# PenguinPi.net
KiCad netlist of a schematic drawn in Altium Designer
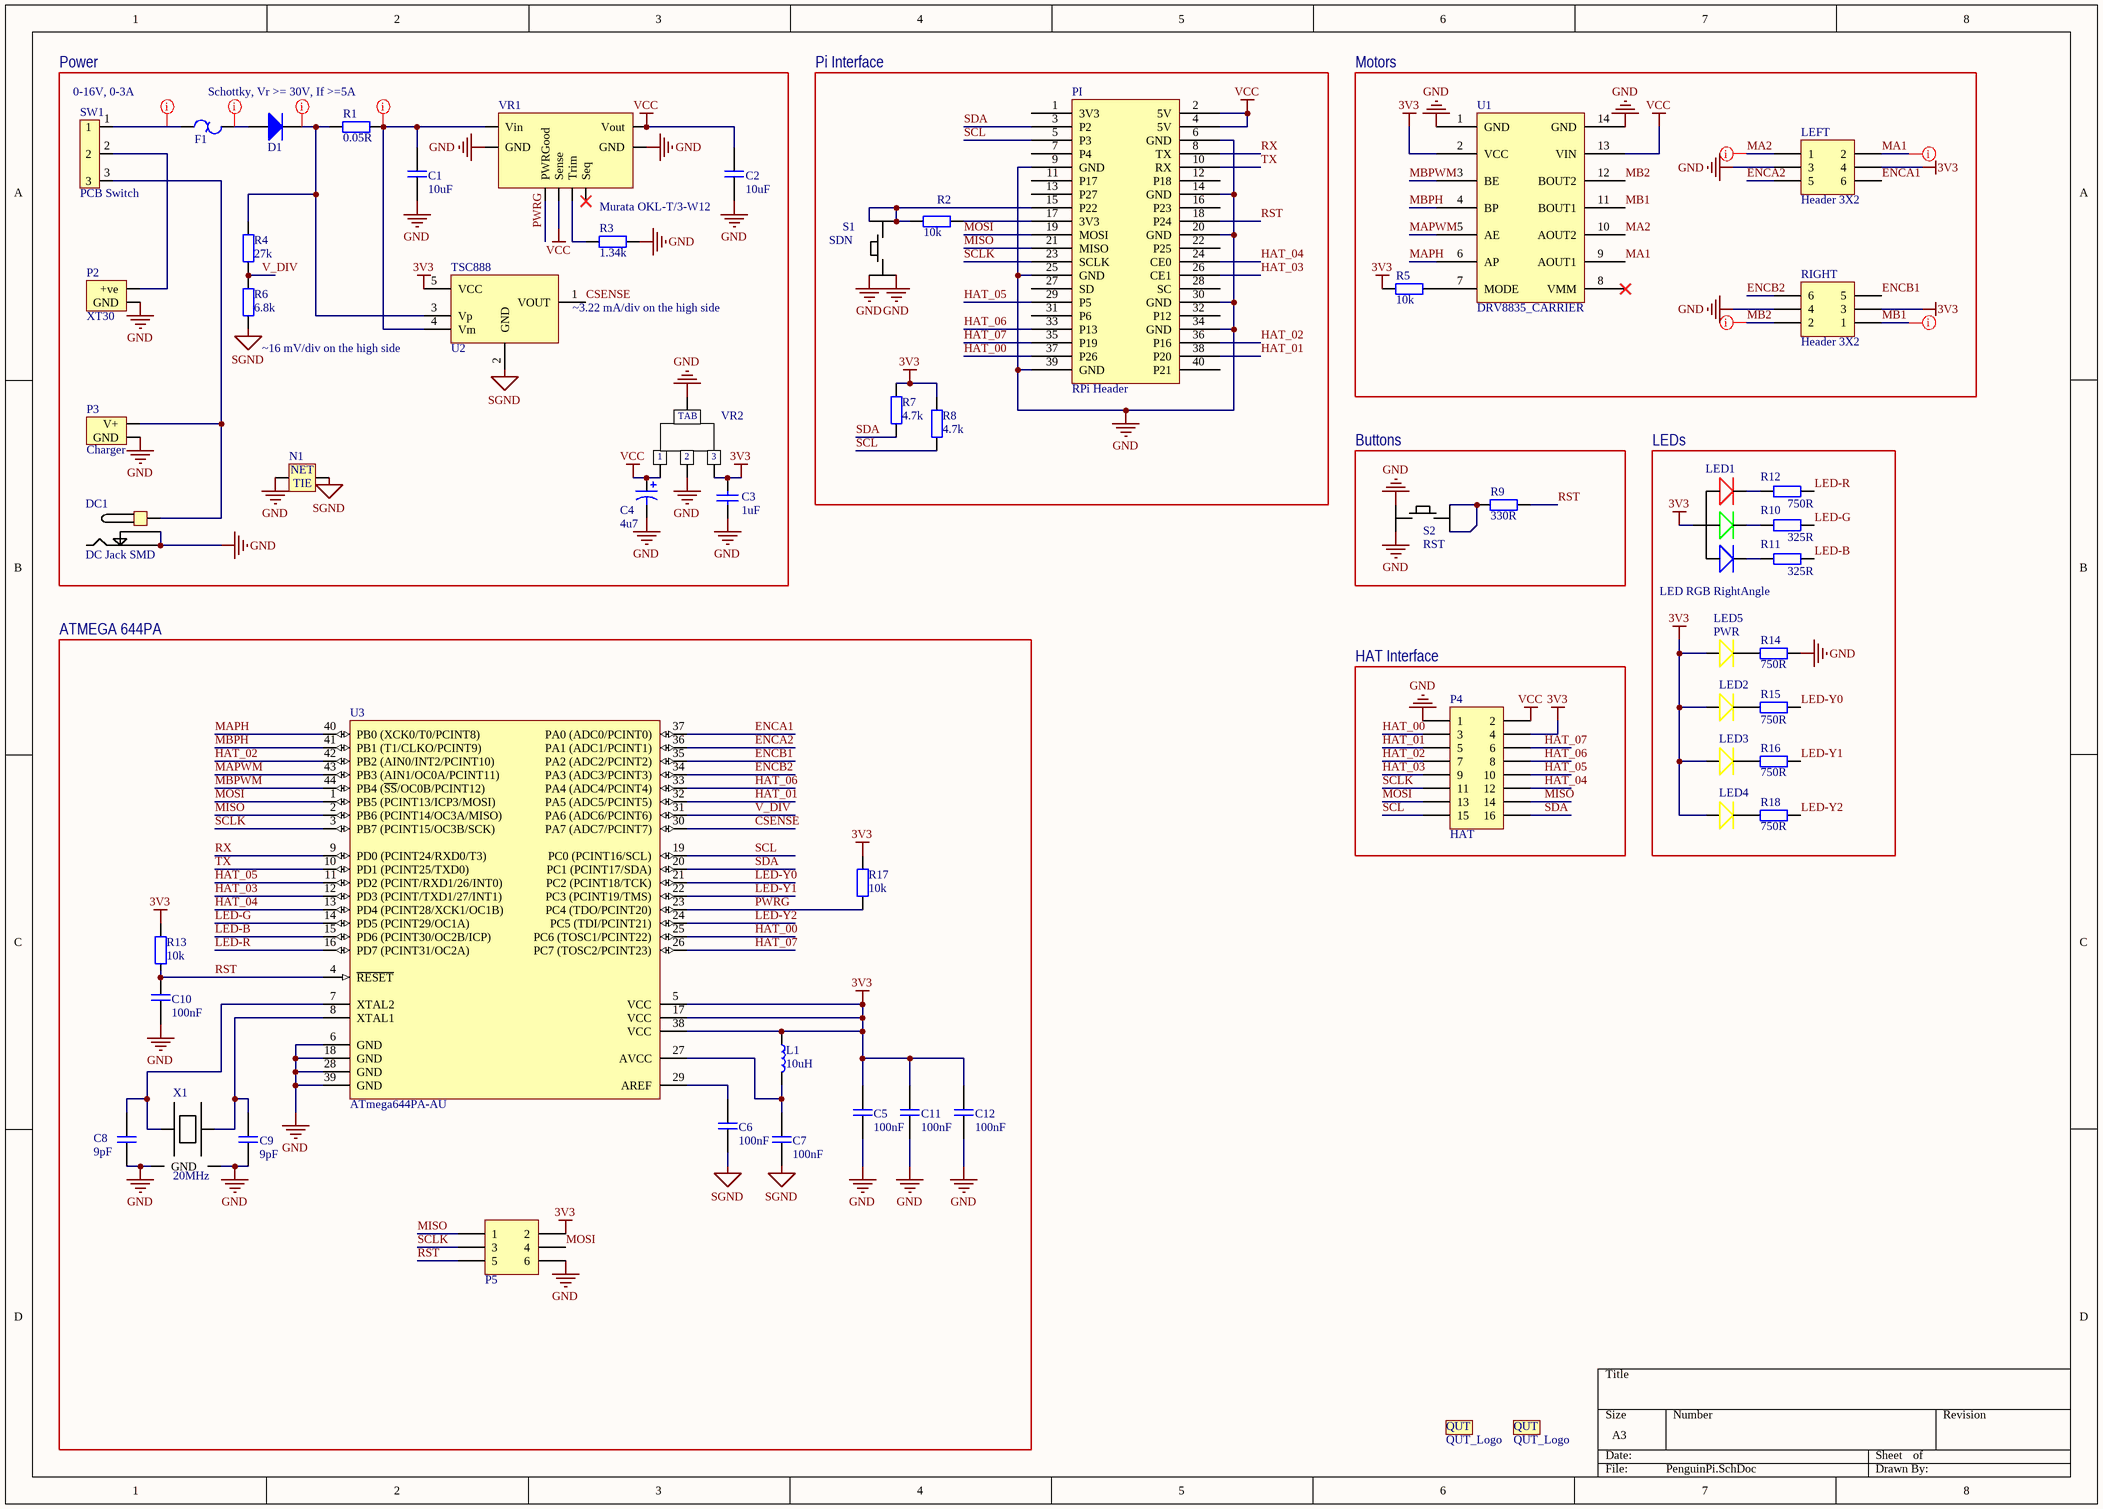
[diagram p0: PenguinPi.SchDoc]

(export (version "E")
  (design (tool "Eeschema 10.0.6"))
  (components
    (comp (ref "C1")
      (value "10uF")
      (footprint "CAPC2012X07N")
      (description "Surface mount capacitor")
      (fields (field (name "Comment") "CAP SMD"))
      (libsource (lib "Penguin") (part "CAP SMD"))
    )
    (comp (ref "C2")
      (value "10uF")
      (footprint "CAPC2012X07N")
      (description "Surface mount capacitor")
      (fields (field (name "Comment") "CAP SMD"))
      (libsource (lib "Penguin") (part "CAP SMD"))
    )
    (comp (ref "C3")
      (value "1uF")
      (footprint "6-0805_M")
      (description "Capacitor")
      (fields (field (name "Comment") "Cap") (field (name "PUBLISHER") "Altium Limited"))
      (libsource (lib "Miscellaneous Devices") (part "Cap"))
    )
    (comp (ref "C4")
      (value "4u7")
      (footprint "6-0805_M")
      (description "Polarized Capacitor (Radial)")
      (fields (field (name "Comment") "Cap Pol1") (field (name "PUBLISHER") "Altium Limited"))
      (libsource (lib "Miscellaneous Devices") (part "Cap Pol1"))
    )
    (comp (ref "C5")
      (value "100nF")
      (footprint "CAPC2012X07N")
      (description "Surface mount capacitor")
      (fields (field (name "Comment") "CAP SMD"))
      (libsource (lib "Penguin") (part "CAP SMD"))
    )
    (comp (ref "C6")
      (value "100nF")
      (footprint "CAPC2012X07N")
      (description "Surface mount capacitor")
      (fields (field (name "Comment") "CAP SMD"))
      (libsource (lib "Penguin") (part "CAP SMD"))
    )
    (comp (ref "C7")
      (value "100nF")
      (footprint "CAPC2012X07N")
      (description "Surface mount capacitor")
      (fields (field (name "Comment") "CAP SMD"))
      (libsource (lib "Penguin") (part "CAP SMD"))
    )
    (comp (ref "C8")
      (value "9pF")
      (footprint "CAPC2012X07N")
      (description "Surface mount capacitor")
      (fields (field (name "Comment") "CAP SMD"))
      (libsource (lib "Penguin") (part "CAP SMD"))
    )
    (comp (ref "C9")
      (value "9pF")
      (footprint "CAPC2012X07N")
      (description "Surface mount capacitor")
      (fields (field (name "Comment") "CAP SMD"))
      (libsource (lib "Penguin") (part "CAP SMD"))
    )
    (comp (ref "C10")
      (value "100nF")
      (footprint "CAPC2012X07N")
      (description "Surface mount capacitor")
      (fields (field (name "Comment") "CAP SMD"))
      (libsource (lib "Penguin") (part "CAP SMD"))
    )
    (comp (ref "C11")
      (value "100nF")
      (footprint "CAPC2012X07N")
      (description "Surface mount capacitor")
      (fields (field (name "Comment") "CAP SMD"))
      (libsource (lib "Penguin") (part "CAP SMD"))
    )
    (comp (ref "C12")
      (value "100nF")
      (footprint "CAPC2012X07N")
      (description "Surface mount capacitor")
      (fields (field (name "Comment") "CAP SMD"))
      (libsource (lib "Penguin") (part "CAP SMD"))
    )
    (comp (ref "D1")
      (value "SMD DIODE")
      (footprint "SODFL470X110-2N")
      (description "Surface mount Diode")
      (libsource (lib "Penguin") (part "SMD DIODE"))
    )
    (comp (ref "DC1")
      (value "DC Jack SMD")
      (footprint "DC Jack SMD")
      (libsource (lib "QUT") (part "DC Jack SMD"))
    )
    (comp (ref "F1")
      (value "RGEF250")
      (footprint "MF-MSMF250/16X-2")
      (description "PPTC Thermal Fuse")
      (libsource (lib "Penguin") (part "RGEF250"))
    )
    (comp (ref "L1")
      (value "10uH")
      (footprint "CM322522")
      (description "Surface Mount Inductor - varying sizes")
      (fields (field (name "Comment") "INDUCTOR SMD"))
      (libsource (lib "Penguin") (part "INDUCTOR SMD"))
    )
    (comp (ref "LED1")
      (value "LED RGB RightAngle")
      (footprint "LED RGB RightAngle")
      (libsource (lib "PenguinPi_v2") (part "LED RGB RightAngle"))
    )
    (comp (ref "LED2")
      (value "~")
      (footprint "LED YELLOW RightAngle")
      (libsource (lib "PenguinPi_v2") (part "LED Yellow RightAngle"))
    )
    (comp (ref "LED3")
      (value "~")
      (footprint "LED YELLOW RightAngle")
      (libsource (lib "PenguinPi_v2") (part "LED Yellow RightAngle"))
    )
    (comp (ref "LED4")
      (value "~")
      (footprint "LED YELLOW RightAngle")
      (libsource (lib "PenguinPi_v2") (part "LED Yellow RightAngle"))
    )
    (comp (ref "LED5")
      (value "PWR")
      (footprint "LED YELLOW RightAngle")
      (libsource (lib "PenguinPi_v2") (part "LED Yellow RightAngle"))
    )
    (comp (ref "LEFT")
      (value "Header 3X2")
      (footprint "HDR2X3")
      (description "Header, 3-Pin, Dual row")
      (fields (field (name "PUBLISHER") "Altium Limited"))
      (libsource (lib "") (part "Header 3X2_1"))
    )
    (comp (ref "LG1") (value "QUT_Logo") (footprint "QUT_Logo") (libsource (lib "Penguin") (part "QUT_Logo")))
    (comp (ref "LG2") (value "QUT_Logo") (footprint "QUT_Logo") (libsource (lib "Penguin") (part "QUT_Logo")))
    (comp (ref "N1")
      (value "NETTIE")
      (footprint "NETTIE-SMD-5mil")
      (libsource (lib "Penguin") (part "NETTIE"))
    )
    (comp (ref "P2") (value "XT30") (footprint "XT30 - PCB mount") (libsource (lib "QUT") (part "XT30")))
    (comp (ref "P3")
      (value "Charger")
      (footprint "Molex SL70553 2 way")
      (fields (field (name "MANUFACTURER") "Molex") (field (name "MANUFACTURER PART NO") "70553-0001"))
      (libsource (lib "QUT") (part "Molex SL 70553 2way"))
    )
    (comp (ref "P4")
      (value "HAT")
      (footprint "HDR2X8")
      (description "Header, 8-Pin, Dual row")
      (fields (field (name "PUBLISHER") "Altium Limited"))
      (libsource (lib "Miscellaneous Connectors") (part "Header 8X2"))
    )
    (comp (ref "P5")
      (value "ISP")
      (footprint "Header 3x2 nonstandard")
      (description "3 by 2 header, staggered pin arrangement")
      (libsource (lib "Penguin") (part "Header 3x2 Staggered"))
    )
    (comp (ref "PI")
      (value "RPi Header")
      (footprint "RPI 2 Header")
      (description "GPIO connector for Raspberry Pi Microcomputer")
      (libsource (lib "Penguin") (part "RPi 2 Header"))
    )
    (comp (ref "R1")
      (value "0.05R")
      (footprint "RESC3216X06M")
      (description "0805 surface mount resistor")
      (fields (field (name "Comment") "RES SMD"))
      (libsource (lib "") (part "RES SMD_2"))
    )
    (comp (ref "R2")
      (value "10k")
      (footprint "RESC2012X07N")
      (description "0805 surface mount resistor")
      (fields (field (name "Comment") "RES SMD"))
      (libsource (lib "Penguin") (part "RES SMD"))
    )
    (comp (ref "R3")
      (value "1.34k")
      (footprint "RESC2012X07N")
      (description "0805 surface mount resistor")
      (fields (field (name "Comment") "RES SMD"))
      (libsource (lib "") (part "RES SMD_3"))
    )
    (comp (ref "R4")
      (value "27k")
      (footprint "RESC2012X07N")
      (description "0805 surface mount resistor")
      (fields (field (name "Comment") "RES SMD"))
      (libsource (lib "") (part "RES SMD_1"))
    )
    (comp (ref "R5")
      (value "10k")
      (footprint "RESC2012X07N")
      (description "0805 surface mount resistor")
      (fields (field (name "Comment") "RES SMD"))
      (libsource (lib "Penguin") (part "RES SMD"))
    )
    (comp (ref "R6")
      (value "6.8k")
      (footprint "RESC2012X07N")
      (description "0805 surface mount resistor")
      (fields (field (name "Comment") "RES SMD"))
      (libsource (lib "") (part "RES SMD_1"))
    )
    (comp (ref "R7")
      (value "4.7k")
      (footprint "RESC2012X07N")
      (description "0805 surface mount resistor")
      (fields (field (name "Comment") "RES SMD"))
      (libsource (lib "") (part "RES SMD_1"))
    )
    (comp (ref "R8")
      (value "4.7k")
      (footprint "RESC2012X07N")
      (description "0805 surface mount resistor")
      (fields (field (name "Comment") "RES SMD"))
      (libsource (lib "") (part "RES SMD_1"))
    )
    (comp (ref "R9")
      (value "330R")
      (footprint "RESC2012X07N")
      (description "0805 surface mount resistor")
      (fields (field (name "Comment") "RES SMD"))
      (libsource (lib "Penguin") (part "RES SMD"))
    )
    (comp (ref "R10")
      (value "325R")
      (footprint "RESC2012X07N")
      (description "0805 surface mount resistor")
      (fields (field (name "Comment") "RES SMD"))
      (libsource (lib "Penguin") (part "RES SMD"))
    )
    (comp (ref "R11")
      (value "325R")
      (footprint "RESC2012X07N")
      (description "0805 surface mount resistor")
      (fields (field (name "Comment") "RES SMD"))
      (libsource (lib "Penguin") (part "RES SMD"))
    )
    (comp (ref "R12")
      (value "750R")
      (footprint "RESC2012X07N")
      (description "0805 surface mount resistor")
      (fields (field (name "Comment") "RES SMD"))
      (libsource (lib "Penguin") (part "RES SMD"))
    )
    (comp (ref "R13")
      (value "10k")
      (footprint "RESC2012X07N")
      (description "0805 surface mount resistor")
      (fields (field (name "Comment") "RES SMD"))
      (libsource (lib "") (part "RES SMD_1"))
    )
    (comp (ref "R14")
      (value "750R")
      (footprint "RESC2012X07N")
      (description "0805 surface mount resistor")
      (fields (field (name "Comment") "RES SMD"))
      (libsource (lib "Penguin") (part "RES SMD"))
    )
    (comp (ref "R15")
      (value "750R")
      (footprint "RESC2012X07N")
      (description "0805 surface mount resistor")
      (fields (field (name "Comment") "RES SMD"))
      (libsource (lib "Penguin") (part "RES SMD"))
    )
    (comp (ref "R16")
      (value "750R")
      (footprint "RESC2012X07N")
      (description "0805 surface mount resistor")
      (fields (field (name "Comment") "RES SMD"))
      (libsource (lib "Penguin") (part "RES SMD"))
    )
    (comp (ref "R17")
      (value "10k")
      (footprint "RESC2012X07N")
      (description "0805 surface mount resistor")
      (fields (field (name "Comment") "RES SMD"))
      (libsource (lib "") (part "RES SMD_1"))
    )
    (comp (ref "R18")
      (value "750R")
      (footprint "RESC2012X07N")
      (description "0805 surface mount resistor")
      (fields (field (name "Comment") "RES SMD"))
      (libsource (lib "Penguin") (part "RES SMD"))
    )
    (comp (ref "RIGHT")
      (value "Header 3X2")
      (footprint "HDR2X3")
      (description "Header, 3-Pin, Dual row")
      (fields (field (name "PUBLISHER") "Altium Limited"))
      (libsource (lib "Miscellaneous Connectors") (part "Header 3X2"))
    )
    (comp (ref "S1")
      (value "SDN")
      (footprint "E-SWITCH-TL3342")
      (description "TL 3342 surface mount pushbutton")
      (libsource (lib "Penguin") (part "E-SWITCH-PUSHBUTTON"))
    )
    (comp (ref "S2")
      (value "RST")
      (footprint "E-SWITCH-TL3342")
      (description "TL 3342 surface mount pushbutton")
      (libsource (lib "Penguin") (part "E-SWITCH-PUSHBUTTON"))
    )
    (comp (ref "SW1")
      (value "PCB Switch")
      (footprint "PCB Switch")
      (libsource (lib "PenguinPi_v2") (part "PCB Switch"))
    )
    (comp (ref "U1")
      (value "DRV8835_CARRIER")
      (footprint "DRV8835_CARRIER")
      (description "DRV8835 Motor Controller")
      (libsource (lib "Penguin") (part "DRV8835_CARRIER"))
    )
    (comp (ref "U2")
      (value "TSC888")
      (footprint "SOT95P280X145-5N")
      (description "Curent Sense Amplifier")
      (libsource (lib "Penguin") (part "TSC888"))
    )
    (comp (ref "U3")
      (value "ATmega644PA-AU")
      (footprint "44A_L")
      (libsource (lib "Altium Content Vault") (part "MC-8B-ATM128-SQ44"))
    )
    (comp (ref "VR1")
      (value "Murata OKL-T/3-W12")
      (footprint "OKL-T/3-W12")
      (libsource (lib "PenguinPi_v2") (part "Murata OKL-T/3-W12"))
    )
    (comp (ref "VR2") (value "FT_SOT223") (footprint "SOT233-4N") (libsource (lib "QUT") (part "FT_SOT223")))
    (comp (ref "X1") (value "20MHz") (footprint "XTAL TSX3225") (libsource (lib "QUT") (part "XTAL ABM3B")))
  )
  (nets
    (net (code "1") (name "/CSENSE") (class "Default")
      (node (ref "U2") (pin "1") (pinfunction "VOUT_1") (pintype "passive"))
      (node (ref "U3") (pin "30") (pinfunction "PA7_(ADC7/PCINT7)_30") (pintype "bidirectional"))
    )
    (net (code "2") (name "/ENCA1") (class "Default")
      (node (ref "LEFT") (pin "6") (pinfunction "6_6") (pintype "passive"))
      (node (ref "U3") (pin "37") (pinfunction "PA0_(ADC0/PCINT0)_37") (pintype "bidirectional"))
    )
    (net (code "3") (name "/ENCA2") (class "Default")
      (node (ref "LEFT") (pin "5") (pinfunction "5_5") (pintype "passive"))
      (node (ref "U3") (pin "36") (pinfunction "PA1_(ADC1/PCINT1)_36") (pintype "bidirectional"))
    )
    (net (code "4") (name "/ENCB1") (class "Default")
      (node (ref "RIGHT") (pin "5") (pinfunction "5_5") (pintype "passive"))
      (node (ref "U3") (pin "35") (pinfunction "PA2_(ADC2/PCINT2)_35") (pintype "bidirectional"))
    )
    (net (code "5") (name "/ENCB2") (class "Default")
      (node (ref "RIGHT") (pin "6") (pinfunction "6_6") (pintype "passive"))
      (node (ref "U3") (pin "34") (pinfunction "PA3_(ADC3/PCINT3)_34") (pintype "bidirectional"))
    )
    (net (code "6") (name "/HAT_00") (class "Default")
      (node (ref "P4") (pin "3") (pinfunction "3_3") (pintype "passive"))
      (node (ref "PI") (pin "37") (pinfunction "P26_37") (pintype "passive"))
      (node (ref "U3") (pin "25") (pinfunction "PC6_(TOSC1/PCINT22)_25") (pintype "bidirectional"))
    )
    (net (code "7") (name "/HAT_01") (class "Default")
      (node (ref "P4") (pin "5") (pinfunction "5_5") (pintype "passive"))
      (node (ref "PI") (pin "38") (pinfunction "P20_38") (pintype "passive"))
      (node (ref "U3") (pin "32") (pinfunction "PA5_(ADC5/PCINT5)_32") (pintype "bidirectional"))
    )
    (net (code "8") (name "/HAT_02") (class "Default")
      (node (ref "P4") (pin "7") (pinfunction "7_7") (pintype "passive"))
      (node (ref "PI") (pin "36") (pinfunction "P16_36") (pintype "passive"))
      (node (ref "U3") (pin "42") (pinfunction "PB2_(AIN0/INT2/PCINT10)_42") (pintype "bidirectional"))
    )
    (net (code "9") (name "/HAT_03") (class "Default")
      (node (ref "P4") (pin "9") (pinfunction "9_9") (pintype "passive"))
      (node (ref "PI") (pin "26") (pinfunction "CE1_26") (pintype "passive"))
      (node (ref "U3") (pin "12") (pinfunction "PD3_(PCINT/TXD1/27/INT1)_12") (pintype "bidirectional"))
    )
    (net (code "10") (name "/HAT_04") (class "Default")
      (node (ref "P4") (pin "12") (pinfunction "12_12") (pintype "passive"))
      (node (ref "PI") (pin "24") (pinfunction "CE0_24") (pintype "passive"))
      (node (ref "U3") (pin "13") (pinfunction "PD4_(PCINT28/XCK1/OC1B)_13") (pintype "bidirectional"))
    )
    (net (code "11") (name "/HAT_05") (class "Default")
      (node (ref "P4") (pin "10") (pinfunction "10_10") (pintype "passive"))
      (node (ref "PI") (pin "29") (pinfunction "P5_29") (pintype "passive"))
      (node (ref "U3") (pin "11") (pinfunction "PD2_(PCINT/RXD1/26/INT0)_11") (pintype "bidirectional"))
    )
    (net (code "12") (name "/HAT_06") (class "Default")
      (node (ref "P4") (pin "8") (pinfunction "8_8") (pintype "passive"))
      (node (ref "PI") (pin "33") (pinfunction "P13_33") (pintype "passive"))
      (node (ref "U3") (pin "33") (pinfunction "PA4_(ADC4/PCINT4)_33") (pintype "bidirectional"))
    )
    (net (code "13") (name "/HAT_07") (class "Default")
      (node (ref "P4") (pin "6") (pinfunction "6_6") (pintype "passive"))
      (node (ref "PI") (pin "35") (pinfunction "P19_35") (pintype "passive"))
      (node (ref "U3") (pin "26") (pinfunction "PC7_(TOSC2/PCINT23)_26") (pintype "bidirectional"))
    )
    (net (code "14") (name "/LED-B") (class "Default")
      (node (ref "R11") (pin "2") (pinfunction "2_2") (pintype "passive"))
      (node (ref "U3") (pin "15") (pinfunction "PD6_(PCINT30/OC2B/ICP)_15") (pintype "bidirectional"))
    )
    (net (code "15") (name "/LED-G") (class "Default")
      (node (ref "R10") (pin "2") (pinfunction "2_2") (pintype "passive"))
      (node (ref "U3") (pin "14") (pinfunction "PD5_(PCINT29/OC1A)_14") (pintype "bidirectional"))
    )
    (net (code "16") (name "/LED-R") (class "Default")
      (node (ref "R12") (pin "2") (pinfunction "2_2") (pintype "passive"))
      (node (ref "U3") (pin "16") (pinfunction "PD7_(PCINT31/OC2A)_16") (pintype "bidirectional"))
    )
    (net (code "17") (name "/LED-Y0") (class "Default")
      (node (ref "R15") (pin "2") (pinfunction "2_2") (pintype "passive"))
      (node (ref "U3") (pin "21") (pinfunction "PC2_(PCINT18/TCK)_21") (pintype "bidirectional"))
    )
    (net (code "18") (name "/LED-Y1") (class "Default")
      (node (ref "R16") (pin "2") (pinfunction "2_2") (pintype "passive"))
      (node (ref "U3") (pin "22") (pinfunction "PC3_(PCINT19/TMS)_22") (pintype "bidirectional"))
    )
    (net (code "19") (name "/LED-Y2") (class "Default")
      (node (ref "R18") (pin "2") (pinfunction "2_2") (pintype "passive"))
      (node (ref "U3") (pin "24") (pinfunction "PC5_(TDI/PCINT21)_24") (pintype "bidirectional"))
    )
    (net (code "20") (name "/MA1") (class "Default")
      (node (ref "LEFT") (pin "2") (pinfunction "2_2") (pintype "passive"))
      (node (ref "U1") (pin "9") (pinfunction "AOUT1_9") (pintype "passive"))
    )
    (net (code "21") (name "/MA2") (class "Default")
      (node (ref "LEFT") (pin "1") (pinfunction "1_1") (pintype "passive"))
      (node (ref "U1") (pin "10") (pinfunction "AOUT2_10") (pintype "passive"))
    )
    (net (code "22") (name "/MAPH") (class "Default")
      (node (ref "U1") (pin "6") (pinfunction "AP_6") (pintype "passive"))
      (node (ref "U3") (pin "40") (pinfunction "PB0_(XCK0/T0/PCINT8)_40") (pintype "bidirectional"))
    )
    (net (code "23") (name "/MAPWM") (class "Default")
      (node (ref "U1") (pin "5") (pinfunction "AE_5") (pintype "passive"))
      (node (ref "U3") (pin "43") (pinfunction "PB3_(AIN1/OC0A/PCINT11)_43") (pintype "bidirectional"))
    )
    (net (code "24") (name "/MB1") (class "Default")
      (node (ref "RIGHT") (pin "1") (pinfunction "1_1") (pintype "passive"))
      (node (ref "U1") (pin "11") (pinfunction "BOUT1_11") (pintype "passive"))
    )
    (net (code "25") (name "/MB2") (class "Default")
      (node (ref "RIGHT") (pin "2") (pinfunction "2_2") (pintype "passive"))
      (node (ref "U1") (pin "12") (pinfunction "BOUT2_12") (pintype "passive"))
    )
    (net (code "26") (name "/MBPH") (class "Default")
      (node (ref "U1") (pin "4") (pinfunction "BP_4") (pintype "passive"))
      (node (ref "U3") (pin "41") (pinfunction "PB1_(T1/CLKO/PCINT9)_41") (pintype "bidirectional"))
    )
    (net (code "27") (name "/MBPWM") (class "Default")
      (node (ref "U1") (pin "3") (pinfunction "BE_3") (pintype "passive"))
      (node (ref "U3") (pin "44") (pinfunction "PB4_(~{SS}/OC0B/PCINT12)_44") (pintype "bidirectional"))
    )
    (net (code "28") (name "/MISO") (class "Default")
      (node (ref "P4") (pin "14") (pinfunction "14_14") (pintype "passive"))
      (node (ref "P5") (pin "1") (pinfunction "1_1") (pintype "passive"))
      (node (ref "PI") (pin "21") (pinfunction "MISO_21") (pintype "passive"))
      (node (ref "U3") (pin "2") (pinfunction "PB6_(PCINT14/OC3A/MISO)_2") (pintype "bidirectional"))
    )
    (net (code "29") (name "/MOSI") (class "Default")
      (node (ref "P4") (pin "13") (pinfunction "13_13") (pintype "passive"))
      (node (ref "P5") (pin "4") (pinfunction "4_4") (pintype "passive"))
      (node (ref "PI") (pin "19") (pinfunction "MOSI_19") (pintype "passive"))
      (node (ref "U3") (pin "1") (pinfunction "PB5_(PCINT13/ICP3/MOSI)_1") (pintype "bidirectional"))
    )
    (net (code "30") (name "/PWRG") (class "Default")
      (node (ref "R17") (pin "1") (pinfunction "1_1") (pintype "passive"))
      (node (ref "U3") (pin "23") (pinfunction "PC4_(TDO/PCINT20)_23") (pintype "bidirectional"))
      (node (ref "VR1") (pin "10") (pinfunction "PWRGood_10") (pintype "passive"))
    )
    (net (code "31") (name "/RST") (class "Default")
      (node (ref "C10") (pin "2") (pinfunction "K_2") (pintype "passive"))
      (node (ref "P5") (pin "5") (pinfunction "5_5") (pintype "passive"))
      (node (ref "PI") (pin "18") (pinfunction "P24_18") (pintype "passive"))
      (node (ref "R13") (pin "1") (pinfunction "1_1") (pintype "passive"))
      (node (ref "R9") (pin "2") (pinfunction "2_2") (pintype "passive"))
      (node (ref "U3") (pin "4") (pinfunction "~{RESET}_4") (pintype "input"))
    )
    (net (code "32") (name "/RX") (class "Default")
      (node (ref "PI") (pin "8") (pinfunction "TX_8") (pintype "passive"))
      (node (ref "U3") (pin "9") (pinfunction "PD0_(PCINT24/RXD0/T3)_9") (pintype "bidirectional"))
    )
    (net (code "33") (name "/SCL") (class "Default")
      (node (ref "P4") (pin "15") (pinfunction "15_15") (pintype "passive"))
      (node (ref "PI") (pin "5") (pinfunction "P3_5") (pintype "passive"))
      (node (ref "R8") (pin "1") (pinfunction "1_1") (pintype "passive"))
      (node (ref "U3") (pin "19") (pinfunction "PC0_(PCINT16/SCL)_19") (pintype "bidirectional"))
    )
    (net (code "34") (name "/SCLK") (class "Default")
      (node (ref "P4") (pin "11") (pinfunction "11_11") (pintype "passive"))
      (node (ref "P5") (pin "3") (pinfunction "3_3") (pintype "passive"))
      (node (ref "PI") (pin "23") (pinfunction "SCLK_23") (pintype "passive"))
      (node (ref "U3") (pin "3") (pinfunction "PB7_(PCINT15/OC3B/SCK)_3") (pintype "bidirectional"))
    )
    (net (code "35") (name "/SDA") (class "Default")
      (node (ref "P4") (pin "16") (pinfunction "16_16") (pintype "passive"))
      (node (ref "PI") (pin "3") (pinfunction "P2_3") (pintype "passive"))
      (node (ref "R7") (pin "1") (pinfunction "1_1") (pintype "passive"))
      (node (ref "U3") (pin "20") (pinfunction "PC1_(PCINT17/SDA)_20") (pintype "bidirectional"))
    )
    (net (code "36") (name "/TX") (class "Default")
      (node (ref "PI") (pin "10") (pinfunction "RX_10") (pintype "passive"))
      (node (ref "U3") (pin "10") (pinfunction "PD1_(PCINT25/TXD0)_10") (pintype "bidirectional"))
    )
    (net (code "37") (name "/V_DIV") (class "Default")
      (node (ref "R4") (pin "1") (pinfunction "1_1") (pintype "passive"))
      (node (ref "R6") (pin "2") (pinfunction "2_2") (pintype "passive"))
      (node (ref "U3") (pin "31") (pinfunction "PA6_(ADC6/PCINT6)_31") (pintype "bidirectional"))
    )
    (net (code "38") (name "3V3") (class "Default")
      (node (ref "C11") (pin "2") (pinfunction "K_2") (pintype "passive"))
      (node (ref "C12") (pin "2") (pinfunction "K_2") (pintype "passive"))
      (node (ref "C3") (pin "2") (pinfunction "2_2") (pintype "passive"))
      (node (ref "C5") (pin "2") (pinfunction "K_2") (pintype "passive"))
      (node (ref "L1") (pin "1") (pinfunction "Anode_1") (pintype "passive"))
      (node (ref "LED1") (pin "2") (pinfunction "ANODE_2") (pintype "passive"))
      (node (ref "LED2") (pin "2") (pinfunction "ANODE_2") (pintype "passive"))
      (node (ref "LED3") (pin "2") (pinfunction "ANODE_2") (pintype "passive"))
      (node (ref "LED4") (pin "2") (pinfunction "ANODE_2") (pintype "passive"))
      (node (ref "LED5") (pin "2") (pinfunction "ANODE_2") (pintype "passive"))
      (node (ref "LEFT") (pin "4") (pinfunction "4_4") (pintype "passive"))
      (node (ref "P4") (pin "4") (pinfunction "4_4") (pintype "passive"))
      (node (ref "P5") (pin "2") (pinfunction "2_2") (pintype "passive"))
      (node (ref "R13") (pin "2") (pinfunction "2_2") (pintype "passive"))
      (node (ref "R17") (pin "2") (pinfunction "2_2") (pintype "passive"))
      (node (ref "R5") (pin "1") (pinfunction "1_1") (pintype "passive"))
      (node (ref "R7") (pin "2") (pinfunction "2_2") (pintype "passive"))
      (node (ref "R8") (pin "2") (pinfunction "2_2") (pintype "passive"))
      (node (ref "RIGHT") (pin "3") (pinfunction "3_3") (pintype "passive"))
      (node (ref "U1") (pin "2") (pinfunction "VCC_2") (pintype "passive"))
      (node (ref "U2") (pin "5") (pinfunction "VCC_5") (pintype "passive"))
      (node (ref "U3") (pin "17") (pinfunction "VCC_17") (pintype "power_in"))
      (node (ref "U3") (pin "38") (pinfunction "VCC_38") (pintype "power_in"))
      (node (ref "U3") (pin "5") (pinfunction "VCC_5") (pintype "power_in"))
      (node (ref "VR2") (pin "3") (pinfunction "3_3") (pintype "passive"))
    )
    (net (code "39") (name "GND") (class "Default")
      (node (ref "C1") (pin "1") (pinfunction "A_1") (pintype "passive"))
      (node (ref "C10") (pin "1") (pinfunction "A_1") (pintype "passive"))
      (node (ref "C11") (pin "1") (pinfunction "A_1") (pintype "passive"))
      (node (ref "C12") (pin "1") (pinfunction "A_1") (pintype "passive"))
      (node (ref "C2") (pin "1") (pinfunction "A_1") (pintype "passive"))
      (node (ref "C3") (pin "1") (pinfunction "1_1") (pintype "passive"))
      (node (ref "C4") (pin "2") (pinfunction "2_2") (pintype "passive"))
      (node (ref "C5") (pin "1") (pinfunction "A_1") (pintype "passive"))
      (node (ref "C8") (pin "1") (pinfunction "A_1") (pintype "passive"))
      (node (ref "C9") (pin "1") (pinfunction "A_1") (pintype "passive"))
      (node (ref "DC1") (pin "2") (pinfunction "2_2") (pintype "passive"))
      (node (ref "DC1") (pin "3") (pinfunction "3_3") (pintype "passive"))
      (node (ref "LEFT") (pin "3") (pinfunction "3_3") (pintype "passive"))
      (node (ref "N1") (pin "1") (pinfunction "1_1") (pintype "passive"))
      (node (ref "P2") (pin "1") (pinfunction "GND_1") (pintype "passive"))
      (node (ref "P3") (pin "1") (pinfunction "GND_1") (pintype "passive"))
      (node (ref "P4") (pin "1") (pinfunction "1_1") (pintype "passive"))
      (node (ref "P5") (pin "6") (pinfunction "6_6") (pintype "passive"))
      (node (ref "PI") (pin "14") (pinfunction "GND_14") (pintype "passive"))
      (node (ref "PI") (pin "20") (pinfunction "GND_20") (pintype "passive"))
      (node (ref "PI") (pin "25") (pinfunction "GND_25") (pintype "passive"))
      (node (ref "PI") (pin "30") (pinfunction "GND_30") (pintype "passive"))
      (node (ref "PI") (pin "34") (pinfunction "GND_34") (pintype "passive"))
      (node (ref "PI") (pin "39") (pinfunction "GND_39") (pintype "passive"))
      (node (ref "PI") (pin "6") (pinfunction "GND_6") (pintype "passive"))
      (node (ref "PI") (pin "9") (pinfunction "GND_9") (pintype "passive"))
      (node (ref "R14") (pin "2") (pinfunction "2_2") (pintype "passive"))
      (node (ref "R3") (pin "1") (pinfunction "1_1") (pintype "passive"))
      (node (ref "RIGHT") (pin "4") (pinfunction "4_4") (pintype "passive"))
      (node (ref "S1") (pin "3") (pinfunction "B'_3") (pintype "passive"))
      (node (ref "S1") (pin "4") (pinfunction "B_4") (pintype "passive"))
      (node (ref "S2") (pin "1") (pinfunction "A_1") (pintype "passive"))
      (node (ref "S2") (pin "2") (pinfunction "A'_2") (pintype "passive"))
      (node (ref "U1") (pin "1") (pinfunction "GND_1") (pintype "passive"))
      (node (ref "U1") (pin "14") (pinfunction "GND_14") (pintype "passive"))
      (node (ref "U3") (pin "18") (pinfunction "GND_18") (pintype "power_in"))
      (node (ref "U3") (pin "28") (pinfunction "GND_28") (pintype "power_in"))
      (node (ref "U3") (pin "39") (pinfunction "GND_39") (pintype "power_in"))
      (node (ref "U3") (pin "6") (pinfunction "GND_6") (pintype "power_in"))
      (node (ref "VR1") (pin "3") (pinfunction "GND_3") (pintype "passive"))
      (node (ref "VR1") (pin "7") (pinfunction "GND_7") (pintype "passive"))
      (node (ref "VR2") (pin "2") (pinfunction "2_2") (pintype "passive"))
      (node (ref "VR2") (pin "4") (pinfunction "4_4") (pintype "passive"))
      (node (ref "X1") (pin "2") (pinfunction "GND_2") (pintype "passive"))
      (node (ref "X1") (pin "4") (pinfunction "GND_4") (pintype "passive"))
    )
    (net (code "40") (name "Net-(C1-K)") (class "Default")
      (node (ref "C1") (pin "2") (pinfunction "K_2") (pintype "passive"))
      (node (ref "R1") (pin "2") (pinfunction "2_2") (pintype "power_in"))
      (node (ref "U2") (pin "4") (pinfunction "Vm_4") (pintype "passive"))
      (node (ref "VR1") (pin "2") (pinfunction "Vin_2") (pintype "passive"))
    )
    (net (code "41") (name "Net-(C6-K)") (class "Default")
      (node (ref "C6") (pin "2") (pinfunction "K_2") (pintype "passive"))
      (node (ref "U3") (pin "29") (pinfunction "AREF_29") (pintype "power_in"))
    )
    (net (code "42") (name "Net-(C7-K)") (class "Default")
      (node (ref "C7") (pin "2") (pinfunction "K_2") (pintype "passive"))
      (node (ref "L1") (pin "2") (pinfunction "Cathode_2") (pintype "passive"))
      (node (ref "U3") (pin "27") (pinfunction "AVCC_27") (pintype "power_in"))
    )
    (net (code "43") (name "Net-(C8-K)") (class "Default")
      (node (ref "C8") (pin "2") (pinfunction "K_2") (pintype "passive"))
      (node (ref "U3") (pin "7") (pinfunction "XTAL2_7") (pintype "passive"))
      (node (ref "X1") (pin "3") (pinfunction "3_3") (pintype "passive"))
    )
    (net (code "44") (name "Net-(C9-K)") (class "Default")
      (node (ref "C9") (pin "2") (pinfunction "K_2") (pintype "passive"))
      (node (ref "U3") (pin "8") (pinfunction "XTAL1_8") (pintype "passive"))
      (node (ref "X1") (pin "1") (pinfunction "1_1") (pintype "passive"))
    )
    (net (code "45") (name "Net-(D1-Pad1)") (class "Default")
      (node (ref "D1") (pin "1") (pinfunction "1_1") (pintype "power_in"))
      (node (ref "F1") (pin "2") (pinfunction "2_2") (pintype "power_in"))
    )
    (net (code "46") (name "Net-(F1-Pad1)") (class "Default")
      (node (ref "F1") (pin "1") (pinfunction "1_1") (pintype "power_in"))
      (node (ref "SW1") (pin "1") (pinfunction "1_1") (pintype "passive"))
    )
    (net (code "47") (name "Net-(LED1-BLUE)") (class "Default")
      (node (ref "LED1") (pin "4") (pinfunction "BLUE_4") (pintype "passive"))
      (node (ref "R11") (pin "1") (pinfunction "1_1") (pintype "passive"))
    )
    (net (code "48") (name "Net-(LED1-GREEN)") (class "Default")
      (node (ref "LED1") (pin "3") (pinfunction "GREEN_3") (pintype "passive"))
      (node (ref "R10") (pin "1") (pinfunction "1_1") (pintype "passive"))
    )
    (net (code "49") (name "Net-(LED1-RED)") (class "Default")
      (node (ref "LED1") (pin "1") (pinfunction "RED_1") (pintype "passive"))
      (node (ref "R12") (pin "1") (pinfunction "1_1") (pintype "passive"))
    )
    (net (code "50") (name "Net-(LED2-YELLOW)") (class "Default")
      (node (ref "LED2") (pin "1") (pinfunction "YELLOW_1") (pintype "passive"))
      (node (ref "R15") (pin "1") (pinfunction "1_1") (pintype "passive"))
    )
    (net (code "51") (name "Net-(LED3-YELLOW)") (class "Default")
      (node (ref "LED3") (pin "1") (pinfunction "YELLOW_1") (pintype "passive"))
      (node (ref "R16") (pin "1") (pinfunction "1_1") (pintype "passive"))
    )
    (net (code "52") (name "Net-(LED4-YELLOW)") (class "Default")
      (node (ref "LED4") (pin "1") (pinfunction "YELLOW_1") (pintype "passive"))
      (node (ref "R18") (pin "1") (pinfunction "1_1") (pintype "passive"))
    )
    (net (code "53") (name "Net-(LED5-YELLOW)") (class "Default")
      (node (ref "LED5") (pin "1") (pinfunction "YELLOW_1") (pintype "passive"))
      (node (ref "R14") (pin "1") (pinfunction "1_1") (pintype "passive"))
    )
    (net (code "54") (name "Net-(P2-+ve)") (class "Default")
      (node (ref "P2") (pin "2") (pinfunction "+ve_2") (pintype "passive"))
      (node (ref "SW1") (pin "2") (pinfunction "2_2") (pintype "passive"))
    )
    (net (code "55") (name "Net-(P3-V+)") (class "Default")
      (node (ref "DC1") (pin "1") (pinfunction "1_1") (pintype "passive"))
      (node (ref "P3") (pin "0") (pinfunction "V+_0") (pintype "passive"))
      (node (ref "SW1") (pin "3") (pinfunction "3_3") (pintype "passive"))
    )
    (net (code "56") (name "Net-(PI-3V3-Pad17)") (class "Default")
      (node (ref "PI") (pin "17") (pinfunction "3V3_17") (pintype "passive"))
      (node (ref "R2") (pin "2") (pinfunction "2_2") (pintype "passive"))
    )
    (net (code "57") (name "Net-(PI-P22)") (class "Default")
      (node (ref "PI") (pin "15") (pinfunction "P22_15") (pintype "passive"))
      (node (ref "R2") (pin "1") (pinfunction "1_1") (pintype "passive"))
      (node (ref "S1") (pin "1") (pinfunction "A_1") (pintype "passive"))
      (node (ref "S1") (pin "2") (pinfunction "A'_2") (pintype "passive"))
    )
    (net (code "58") (name "Net-(S2-B')") (class "Default")
      (node (ref "R9") (pin "1") (pinfunction "1_1") (pintype "passive"))
      (node (ref "S2") (pin "3") (pinfunction "B'_3") (pintype "passive"))
      (node (ref "S2") (pin "4") (pinfunction "B_4") (pintype "passive"))
    )
    (net (code "59") (name "Net-(U1-MODE)") (class "Default")
      (node (ref "R5") (pin "2") (pinfunction "2_2") (pintype "passive"))
      (node (ref "U1") (pin "7") (pinfunction "MODE_7") (pintype "passive"))
    )
    (net (code "60") (name "Net-(U2-Vp)") (class "Default")
      (node (ref "D1") (pin "2") (pinfunction "2_2") (pintype "power_in"))
      (node (ref "R1") (pin "1") (pinfunction "1_1") (pintype "power_in"))
      (node (ref "R4") (pin "2") (pinfunction "2_2") (pintype "passive"))
      (node (ref "U2") (pin "3") (pinfunction "Vp_3") (pintype "passive"))
    )
    (net (code "61") (name "Net-(VR1-Trim)") (class "Default")
      (node (ref "R3") (pin "2") (pinfunction "2_2") (pintype "passive"))
      (node (ref "VR1") (pin "6") (pinfunction "Trim_6") (pintype "passive"))
    )
    (net (code "62") (name "SGND") (class "Default")
      (node (ref "C6") (pin "1") (pinfunction "A_1") (pintype "passive"))
      (node (ref "C7") (pin "1") (pinfunction "A_1") (pintype "passive"))
      (node (ref "N1") (pin "2") (pinfunction "2_2") (pintype "passive"))
      (node (ref "R6") (pin "1") (pinfunction "1_1") (pintype "passive"))
      (node (ref "U2") (pin "2") (pinfunction "GND_2") (pintype "passive"))
    )
    (net (code "63") (name "VCC") (class "Default")
      (node (ref "C2") (pin "2") (pinfunction "K_2") (pintype "passive"))
      (node (ref "C4") (pin "1") (pinfunction "1_1") (pintype "passive"))
      (node (ref "P4") (pin "2") (pinfunction "2_2") (pintype "passive"))
      (node (ref "PI") (pin "2") (pinfunction "5V_2") (pintype "passive"))
      (node (ref "PI") (pin "4") (pinfunction "5V_4") (pintype "passive"))
      (node (ref "U1") (pin "13") (pinfunction "VIN_13") (pintype "passive"))
      (node (ref "VR1") (pin "4") (pinfunction "Vout_4") (pintype "passive"))
      (node (ref "VR1") (pin "5") (pinfunction "Sense_5") (pintype "passive"))
      (node (ref "VR2") (pin "1") (pinfunction "1_1") (pintype "passive"))
    )
    (net (code "64") (name "unconnected-(PI-3V3-Pad1)") (class "Default")
      (node (ref "PI") (pin "1") (pinfunction "3V3_1") (pintype "passive"))
    )
    (net (code "65") (name "unconnected-(PI-P4-Pad7)") (class "Default")
      (node (ref "PI") (pin "7") (pinfunction "P4_7") (pintype "passive"))
    )
    (net (code "66") (name "unconnected-(PI-P6-Pad31)") (class "Default")
      (node (ref "PI") (pin "31") (pinfunction "P6_31") (pintype "passive"))
    )
    (net (code "67") (name "unconnected-(PI-P12-Pad32)") (class "Default")
      (node (ref "PI") (pin "32") (pinfunction "P12_32") (pintype "passive"))
    )
    (net (code "68") (name "unconnected-(PI-P17-Pad11)") (class "Default")
      (node (ref "PI") (pin "11") (pinfunction "P17_11") (pintype "passive"))
    )
    (net (code "69") (name "unconnected-(PI-P18-Pad12)") (class "Default")
      (node (ref "PI") (pin "12") (pinfunction "P18_12") (pintype "passive"))
    )
    (net (code "70") (name "unconnected-(PI-P21-Pad40)") (class "Default")
      (node (ref "PI") (pin "40") (pinfunction "P21_40") (pintype "passive"))
    )
    (net (code "71") (name "unconnected-(PI-P23-Pad16)") (class "Default")
      (node (ref "PI") (pin "16") (pinfunction "P23_16") (pintype "passive"))
    )
    (net (code "72") (name "unconnected-(PI-P25-Pad22)") (class "Default")
      (node (ref "PI") (pin "22") (pinfunction "P25_22") (pintype "passive"))
    )
    (net (code "73") (name "unconnected-(PI-P27-Pad13)") (class "Default")
      (node (ref "PI") (pin "13") (pinfunction "P27_13") (pintype "passive"))
    )
    (net (code "74") (name "unconnected-(PI-SC-Pad28)") (class "Default")
      (node (ref "PI") (pin "28") (pinfunction "SC_28") (pintype "passive"))
    )
    (net (code "75") (name "unconnected-(PI-SD-Pad27)") (class "Default")
      (node (ref "PI") (pin "27") (pinfunction "SD_27") (pintype "passive"))
    )
    (net (code "76") (name "unconnected-(U1-VMM-Pad8)") (class "Default")
      (node (ref "U1") (pin "8") (pinfunction "VMM_8") (pintype "passive+no_connect"))
    )
    (net (code "77") (name "unconnected-(VR1-Seq-Pad9)") (class "Default")
      (node (ref "VR1") (pin "9") (pinfunction "Seq_9") (pintype "passive+no_connect"))
    )
  )
)
